# Indicators.net
KiCad netlist of a schematic drawn in Altium Designer
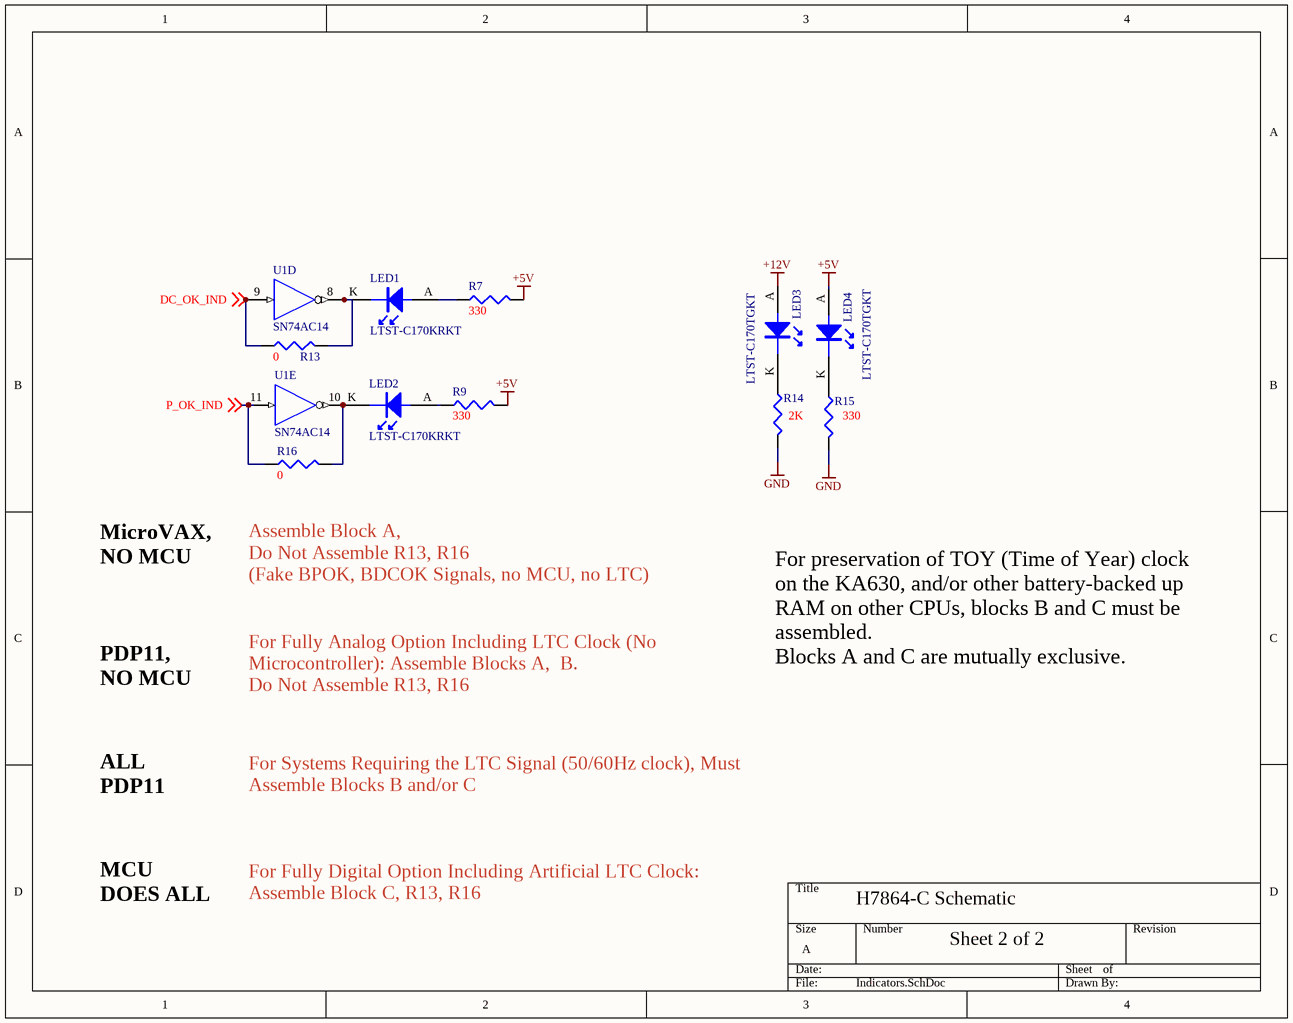
[diagram p0: Indicators.SchDoc]

(export (version "E")
  (design (tool "Eeschema 10.0.6"))
  (components
    (comp (ref "LED1")
      (value "LTST-C170KRKT")
      (footprint "LTST-C170")
      (libsource (lib "TRA1404(DIFT2)") (part "LED"))
    )
    (comp (ref "LED2")
      (value "LTST-C170KRKT")
      (footprint "LTST-C170")
      (libsource (lib "TRA1404(DIFT2)") (part "LED"))
    )
    (comp (ref "LED3")
      (value "LTST-C170TGKT")
      (footprint "LTST-C170")
      (libsource (lib "TRA1404(DIFT2)") (part "LED"))
    )
    (comp (ref "LED4")
      (value "LTST-C170TGKT")
      (footprint "LTST-C170")
      (libsource (lib "TRA1404(DIFT2)") (part "LED"))
    )
    (comp (ref "R7")
      (value "330")
      (footprint "2012[0805]")
      (description "Resistor")
      (fields (field (name "PUBLISHER") "Altium Limited"))
      (libsource (lib "WS Controller") (part "Res3"))
    )
    (comp (ref "R9")
      (value "330")
      (footprint "2012[0805]")
      (description "Resistor")
      (fields (field (name "PUBLISHER") "Altium Limited"))
      (libsource (lib "WS Controller") (part "Res3"))
    )
    (comp (ref "R13")
      (value "0")
      (footprint "2012[0805]")
      (description "Resistor")
      (fields (field (name "Comment") "CRCW080547K0FKEA") (field (name "PUBLISHER") "Altium Limited"))
      (libsource (lib "WS Controller") (part "Res3"))
    )
    (comp (ref "R14")
      (value "2K")
      (footprint "2012[0805]")
      (description "Resistor")
      (fields (field (name "PUBLISHER") "Altium Limited"))
      (libsource (lib "WS Controller") (part "Res3"))
    )
    (comp (ref "R15")
      (value "330")
      (footprint "2012[0805]")
      (description "Resistor")
      (fields (field (name "PUBLISHER") "Altium Limited"))
      (libsource (lib "WS Controller") (part "Res3"))
    )
    (comp (ref "R16")
      (value "0")
      (footprint "2012[0805]")
      (description "Resistor")
      (fields (field (name "Comment") "CRCW080547K0FKEA") (field (name "PUBLISHER") "Altium Limited"))
      (libsource (lib "WS Controller") (part "Res3"))
    )
    (comp (ref "U1")
      (value "SN74AC14")
      (footprint "J014")
      (description "Hex Schmitt-Trigger Inverter")
      (fields (field (name "PUBLISHER") "Altium Limited"))
      (libsource (lib "TI Logic Gate 1") (part "SN74AHCT14D"))
    )
  )
  (nets
    (net (code "1") (name "+5V") (class "Default")
      (node (ref "LED4") (pin "A") (pinfunction "2_A") (pintype "passive"))
      (node (ref "R7") (pin "2") (pinfunction "2_2") (pintype "passive"))
      (node (ref "R9") (pin "2") (pinfunction "2_2") (pintype "passive"))
    )
    (net (code "2") (name "+12V") (class "Default")
      (node (ref "LED3") (pin "A") (pinfunction "2_A") (pintype "passive"))
    )
    (net (code "3") (name "DC_OK_IND") (class "Default")
      (node (ref "R13") (pin "1") (pinfunction "1_1") (pintype "passive"))
      (node (ref "U1") (pin "9") (pinfunction "A_9") (pintype "input"))
    )
    (net (code "4") (name "GND") (class "Default")
      (node (ref "R14") (pin "2") (pinfunction "2_2") (pintype "passive"))
      (node (ref "R15") (pin "2") (pinfunction "2_2") (pintype "passive"))
      (node (ref "U1") (pin "7") (pinfunction "GND_7") (pintype "power_in"))
    )
    (net (code "5") (name "Net-(LED1-1)") (class "Default")
      (node (ref "LED1") (pin "K") (pinfunction "1_K") (pintype "passive"))
      (node (ref "R13") (pin "2") (pinfunction "2_2") (pintype "passive"))
      (node (ref "U1") (pin "8") (pinfunction "Y_8") (pintype "output"))
    )
    (net (code "6") (name "Net-(LED1-2)") (class "Default")
      (node (ref "LED1") (pin "A") (pinfunction "2_A") (pintype "passive"))
      (node (ref "R7") (pin "1") (pinfunction "1_1") (pintype "passive"))
    )
    (net (code "7") (name "Net-(LED2-1)") (class "Default")
      (node (ref "LED2") (pin "K") (pinfunction "1_K") (pintype "passive"))
      (node (ref "R16") (pin "2") (pinfunction "2_2") (pintype "passive"))
      (node (ref "U1") (pin "10") (pinfunction "Y_10") (pintype "output"))
    )
    (net (code "8") (name "Net-(LED2-2)") (class "Default")
      (node (ref "LED2") (pin "A") (pinfunction "2_A") (pintype "passive"))
      (node (ref "R9") (pin "1") (pinfunction "1_1") (pintype "passive"))
    )
    (net (code "9") (name "Net-(LED3-1)") (class "Default")
      (node (ref "LED3") (pin "K") (pinfunction "1_K") (pintype "passive"))
      (node (ref "R14") (pin "1") (pinfunction "1_1") (pintype "passive"))
    )
    (net (code "10") (name "Net-(LED4-1)") (class "Default")
      (node (ref "LED4") (pin "K") (pinfunction "1_K") (pintype "passive"))
      (node (ref "R15") (pin "1") (pinfunction "1_1") (pintype "passive"))
    )
    (net (code "11") (name "P_OK_IND") (class "Default")
      (node (ref "R16") (pin "1") (pinfunction "1_1") (pintype "passive"))
      (node (ref "U1") (pin "11") (pinfunction "A_11") (pintype "input"))
    )
    (net (code "12") (name "VCC") (class "Default")
      (node (ref "U1") (pin "14") (pinfunction "VCC_14") (pintype "power_in"))
    )
  )
)
